# Raspberry_pi_shild_v1.net
KiCad netlist of a schematic drawn in EAGLE
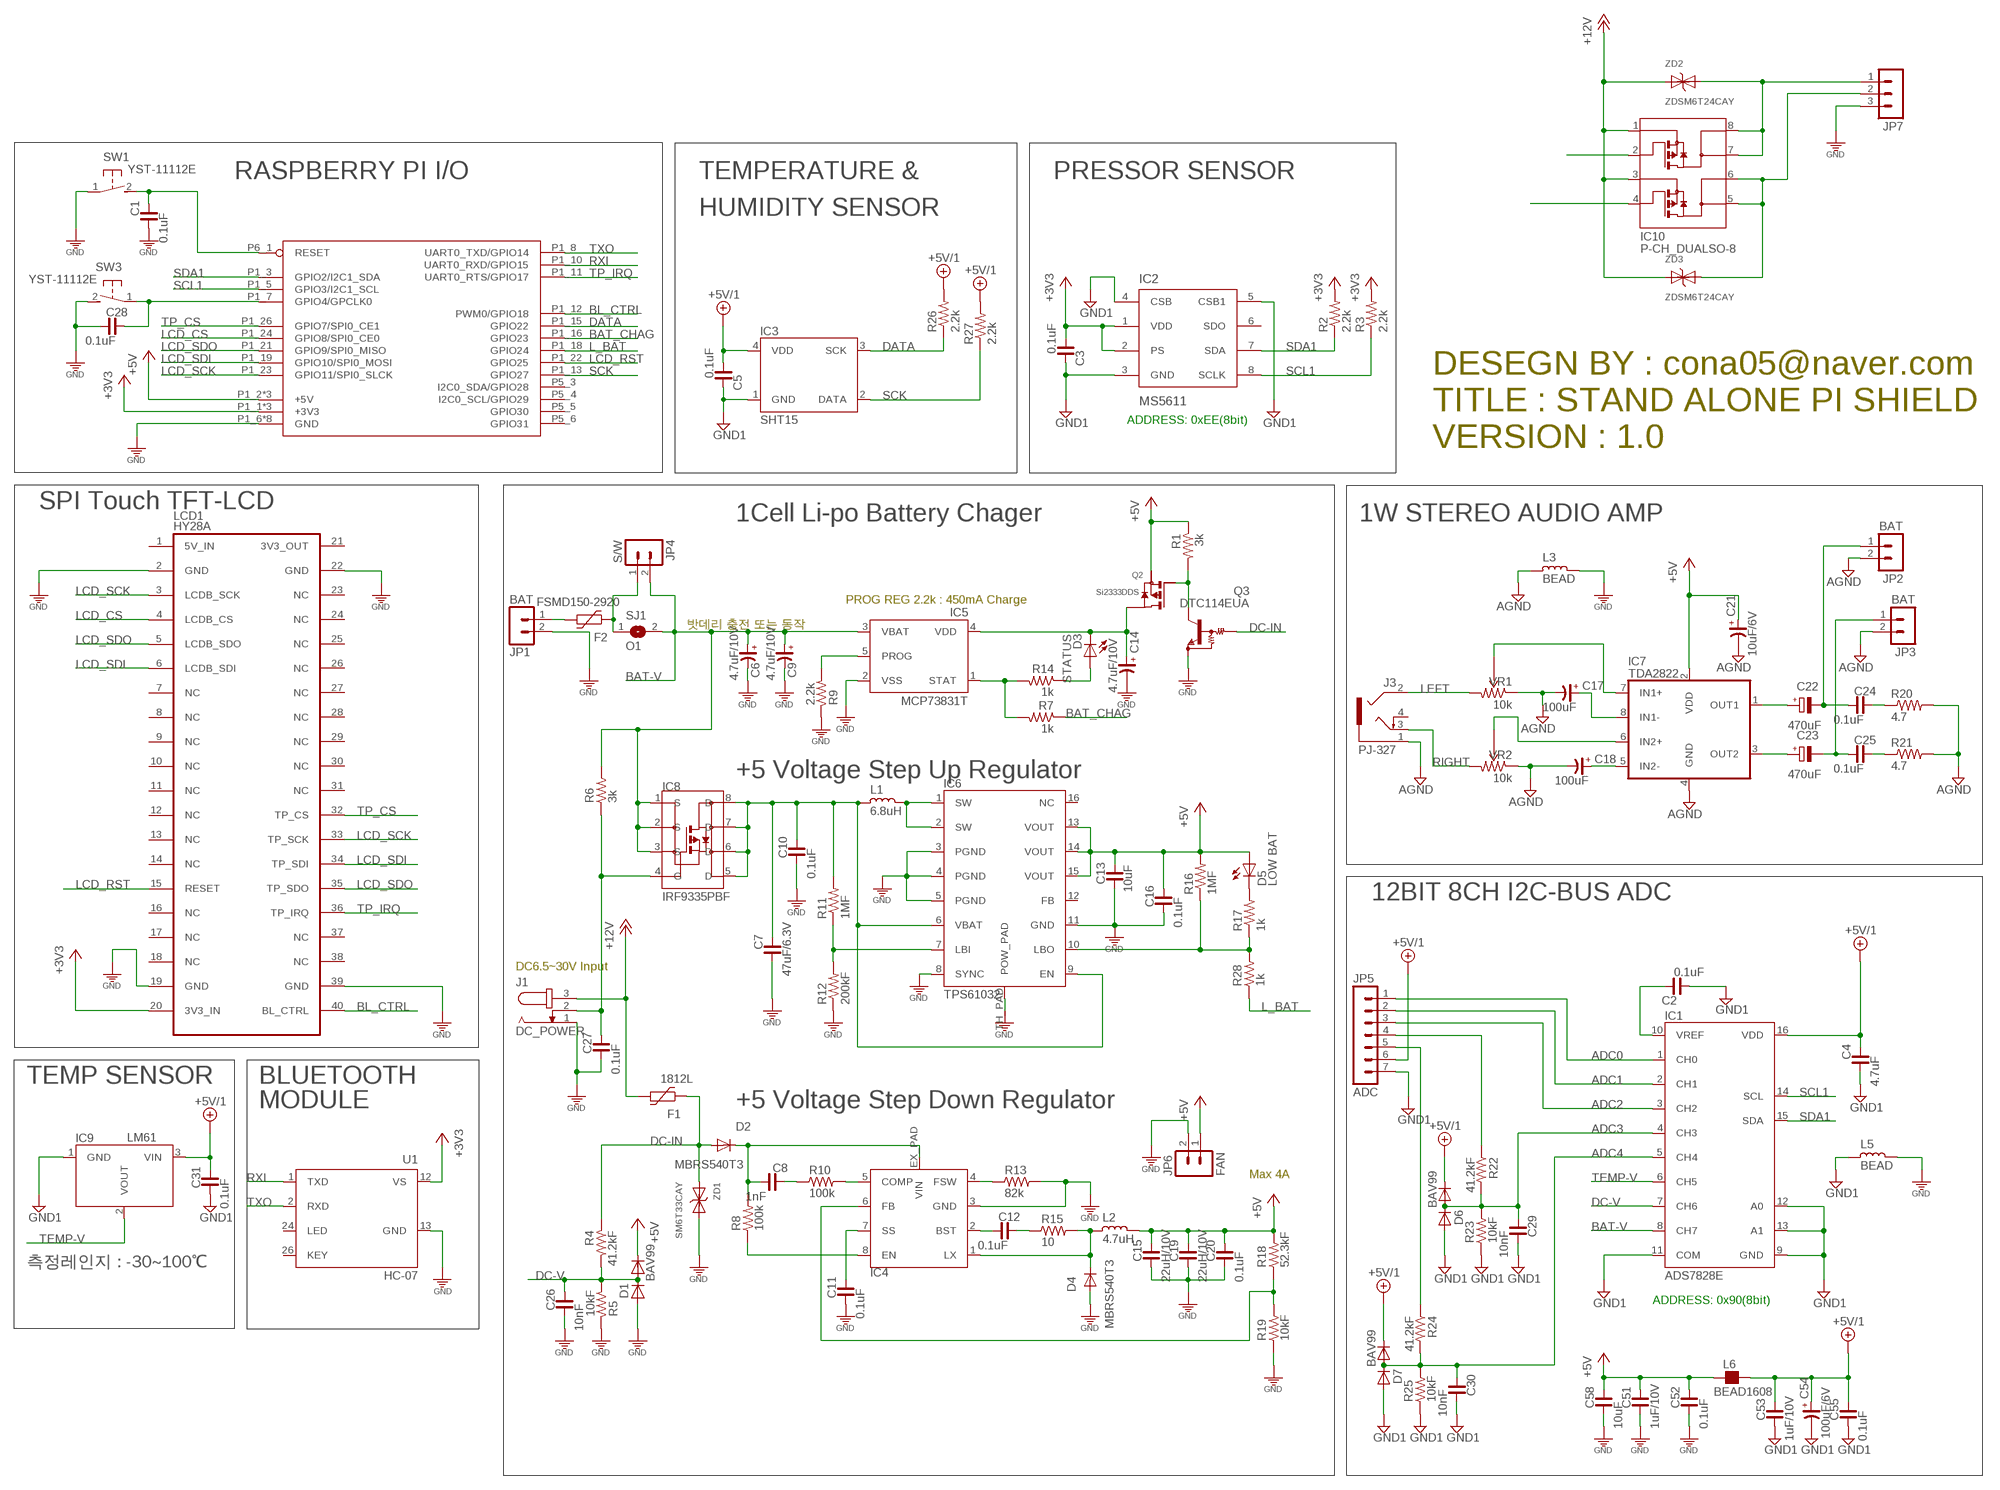
[diagram p0: schematic, sheet 1]

(export (version "E")
  (design (tool "Eeschema 10.0.6"))
  (components
    (comp (ref "C1")
      (value "0.1uF")
      (footprint "eagle-import:C0603")
      (libsource (lib "eagle-import") (part "C_0603"))
    )
    (comp (ref "C2")
      (value "0.1uF")
      (footprint "eagle-import:C0603")
      (libsource (lib "eagle-import") (part "C_0603"))
    )
    (comp (ref "C3")
      (value "0.1uF")
      (footprint "eagle-import:C0603")
      (libsource (lib "eagle-import") (part "C_0603"))
    )
    (comp (ref "C4")
      (value "4.7uF")
      (footprint "eagle-import:C0805")
      (libsource (lib "eagle-import") (part "C_0805"))
    )
    (comp (ref "C5")
      (value "0.1uF")
      (footprint "eagle-import:C0603")
      (libsource (lib "eagle-import") (part "C_0603"))
    )
    (comp (ref "C6")
      (value "4.7uF/10V")
      (footprint "eagle-import:C3216-18_T")
      (libsource (lib "eagle-import") (part "CP_3216-18"))
    )
    (comp (ref "C7")
      (value "47uF/6.3V")
      (footprint "eagle-import:C3216")
      (libsource (lib "eagle-import") (part "C_3216"))
    )
    (comp (ref "C8")
      (value "1nF")
      (footprint "eagle-import:C0603")
      (libsource (lib "eagle-import") (part "C_0603"))
    )
    (comp (ref "C9")
      (value "4.7uF/10V")
      (footprint "eagle-import:C3216-18_T")
      (libsource (lib "eagle-import") (part "CP_3216-18"))
    )
    (comp (ref "C10")
      (value "0.1uF")
      (footprint "eagle-import:C0603")
      (libsource (lib "eagle-import") (part "C_0603"))
    )
    (comp (ref "C11")
      (value "0.1uF")
      (footprint "eagle-import:C0603")
      (libsource (lib "eagle-import") (part "C_0603"))
    )
    (comp (ref "C12")
      (value "0.1uF")
      (footprint "eagle-import:C0603")
      (libsource (lib "eagle-import") (part "C_0603"))
    )
    (comp (ref "C13")
      (value "10uF")
      (footprint "eagle-import:C2012")
      (libsource (lib "eagle-import") (part "C_2012"))
    )
    (comp (ref "C14")
      (value "4.7uF/10V")
      (footprint "eagle-import:C3216-18_T")
      (libsource (lib "eagle-import") (part "CP_3216-18"))
    )
    (comp (ref "C15")
      (value "22uH/10V")
      (footprint "eagle-import:C3216")
      (libsource (lib "eagle-import") (part "C_3216"))
    )
    (comp (ref "C16")
      (value "0.1uF")
      (footprint "eagle-import:C0603")
      (libsource (lib "eagle-import") (part "C_0603"))
    )
    (comp (ref "C17")
      (value "100uF")
      (footprint "eagle-import:C3528-21_T")
      (libsource (lib "eagle-import") (part "CP_3528-21"))
    )
    (comp (ref "C18")
      (value "100uF")
      (footprint "eagle-import:C3528-21_T")
      (libsource (lib "eagle-import") (part "CP_3528-21"))
    )
    (comp (ref "C19")
      (value "22uH/10V")
      (footprint "eagle-import:C3216")
      (libsource (lib "eagle-import") (part "C_3216"))
    )
    (comp (ref "C20")
      (value "0.1uF")
      (footprint "eagle-import:C0603")
      (libsource (lib "eagle-import") (part "C_0603"))
    )
    (comp (ref "C21")
      (value "10uF/6V")
      (footprint "eagle-import:C3216-18_T")
      (libsource (lib "eagle-import") (part "CP_3216-18"))
    )
    (comp (ref "C22")
      (value "470uF")
      (footprint "eagle-import:D_7343-31W")
      (libsource (lib "eagle-import") (part "CPOL-EUD/7343-31W"))
    )
    (comp (ref "C23")
      (value "470uF")
      (footprint "eagle-import:D_7343-31W")
      (libsource (lib "eagle-import") (part "CPOL-EUD/7343-31W"))
    )
    (comp (ref "C24")
      (value "0.1uF")
      (footprint "eagle-import:C0603")
      (libsource (lib "eagle-import") (part "C_0603"))
    )
    (comp (ref "C25")
      (value "0.1uF")
      (footprint "eagle-import:C0603")
      (libsource (lib "eagle-import") (part "C_0603"))
    )
    (comp (ref "C26")
      (value "10nF")
      (footprint "eagle-import:C0603")
      (libsource (lib "eagle-import") (part "C_0603"))
    )
    (comp (ref "C27")
      (value "0.1uF")
      (footprint "eagle-import:C0603")
      (libsource (lib "eagle-import") (part "C_0603"))
    )
    (comp (ref "C28")
      (value "0.1uF")
      (footprint "eagle-import:C0603")
      (libsource (lib "eagle-import") (part "C_0603"))
    )
    (comp (ref "C29")
      (value "10nF")
      (footprint "eagle-import:C0603")
      (libsource (lib "eagle-import") (part "C_0603"))
    )
    (comp (ref "C30")
      (value "10nF")
      (footprint "eagle-import:C0603")
      (libsource (lib "eagle-import") (part "C_0603"))
    )
    (comp (ref "C31")
      (value "0.1uF")
      (footprint "eagle-import:C0603")
      (libsource (lib "eagle-import") (part "C_0603"))
    )
    (comp (ref "C51")
      (value "1uF/10V")
      (footprint "eagle-import:C0603")
      (libsource (lib "eagle-import") (part "C_0603"))
    )
    (comp (ref "C52")
      (value "0.1uF")
      (footprint "eagle-import:C0603")
      (libsource (lib "eagle-import") (part "C_0603"))
    )
    (comp (ref "C53")
      (value "1uF/10V")
      (footprint "eagle-import:C0603")
      (libsource (lib "eagle-import") (part "C_0603"))
    )
    (comp (ref "C54")
      (value "100uF/6V")
      (footprint "eagle-import:C3528-21_T")
      (libsource (lib "eagle-import") (part "CP_3528-21"))
    )
    (comp (ref "C55")
      (value "0.1uF")
      (footprint "eagle-import:C0603")
      (libsource (lib "eagle-import") (part "C_0603"))
    )
    (comp (ref "C58")
      (value "10uF")
      (footprint "eagle-import:C0805")
      (libsource (lib "eagle-import") (part "C_0805"))
    )
    (comp (ref "D1")
      (value "BAV99")
      (footprint "eagle-import:SOT23")
      (libsource (lib "eagle-import") (part "BAV99"))
    )
    (comp (ref "D2")
      (value "MBRS540T3")
      (footprint "eagle-import:SMC")
      (libsource (lib "eagle-import") (part "DIODE-SMC"))
    )
    (comp (ref "D3")
      (value "STATUS")
      (footprint "eagle-import:LED3MM")
      (libsource (lib "eagle-import") (part "LED3MM"))
    )
    (comp (ref "D4")
      (value "MBRS540T3")
      (footprint "eagle-import:SMC")
      (libsource (lib "eagle-import") (part "DIODE-SMC"))
    )
    (comp (ref "D5")
      (value "LOW BAT")
      (footprint "eagle-import:LED3MM")
      (libsource (lib "eagle-import") (part "LED3MM"))
    )
    (comp (ref "D6")
      (value "BAV99")
      (footprint "eagle-import:SOT23")
      (libsource (lib "eagle-import") (part "BAV99"))
    )
    (comp (ref "D7")
      (value "BAV99")
      (footprint "eagle-import:SOT23")
      (libsource (lib "eagle-import") (part "BAV99"))
    )
    (comp (ref "F1")
      (value "1812L")
      (footprint "eagle-import:1812L")
      (libsource (lib "eagle-import") (part "1812L"))
    )
    (comp (ref "F2")
      (value "FSMD150-2920")
      (footprint "eagle-import:1812L")
      (libsource (lib "eagle-import") (part "1812L"))
    )
    (comp (ref "IC1")
      (value "ADS7828E")
      (footprint "eagle-import:R-PDSO-G16")
      (libsource (lib "eagle-import") (part "ADS7828"))
    )
    (comp (ref "IC2")
      (value "MS5611")
      (footprint "eagle-import:LCP8")
      (libsource (lib "eagle-import") (part "MS5611"))
    )
    (comp (ref "IC3")
      (value "SHT15")
      (footprint "eagle-import:SHT1X")
      (libsource (lib "eagle-import") (part "SHT15"))
    )
    (comp (ref "IC4")
      (value "AOZ1284PI")
      (footprint "eagle-import:S08-EP1")
      (libsource (lib "eagle-import") (part "AOZ1284PI"))
    )
    (comp (ref "IC5")
      (value "MCP73831T")
      (footprint "eagle-import:SOT23-5L@1")
      (libsource (lib "eagle-import") (part "MCP73831T"))
    )
    (comp (ref "IC6")
      (value "TPS61032")
      (footprint "eagle-import:R-PDSO-G16-TH_PAD")
      (libsource (lib "eagle-import") (part "TPS61032"))
    )
    (comp (ref "IC7")
      (value "TDA2822")
      (footprint "eagle-import:SO08")
      (libsource (lib "eagle-import") (part "TDA2822"))
    )
    (comp (ref "IC8")
      (value "IRF9335PBF")
      (footprint "eagle-import:SO08")
      (libsource (lib "eagle-import") (part "HEXFET_P"))
    )
    (comp (ref "IC9")
      (value "LM61")
      (footprint "eagle-import:TO92-")
      (libsource (lib "eagle-import") (part "LM61"))
    )
    (comp (ref "IC10")
      (value "P-CH_DUALSO-8")
      (footprint "eagle-import:SO08-1")
      (libsource (lib "eagle-import") (part "P-CH_DUALSO-8"))
    )
    (comp (ref "J1")
      (value "DC_POWER")
      (footprint "eagle-import:SPC4077")
      (libsource (lib "eagle-import") (part "JACK-PLUG0"))
    )
    (comp (ref "J3")
      (value "PJ-327")
      (footprint "eagle-import:PJ-327-2")
      (libsource (lib "eagle-import") (part "AUDIO_JACK2"))
    )
    (comp (ref "JP1")
      (value "BAT")
      (footprint "eagle-import:MA02-MOL-R")
      (libsource (lib "eagle-import") (part "MA02MOL-R"))
    )
    (comp (ref "JP2")
      (value "BAT")
      (footprint "eagle-import:MA02-MOL-R")
      (libsource (lib "eagle-import") (part "MA02MOL-R"))
    )
    (comp (ref "JP3")
      (value "BAT")
      (footprint "eagle-import:MA02-MOL-R")
      (libsource (lib "eagle-import") (part "MA02MOL-R"))
    )
    (comp (ref "JP4")
      (value "S/W")
      (footprint "eagle-import:MA02-MOL-R")
      (libsource (lib "eagle-import") (part "MA02MOL-R"))
    )
    (comp (ref "JP5")
      (value "ADC")
      (footprint "eagle-import:MA07-1T")
      (libsource (lib "eagle-import") (part "MA07-1"))
    )
    (comp (ref "JP6")
      (value "FAN")
      (footprint "eagle-import:MA02-MOL-R")
      (libsource (lib "eagle-import") (part "MA02MOL-R"))
    )
    (comp (ref "JP7")
      (value "MA03-1SMALL")
      (footprint "eagle-import:MA03-1-S")
      (libsource (lib "eagle-import") (part "MA03-1SMALL"))
    )
    (comp (ref "L1")
      (value "6.8uH")
      (footprint "eagle-import:L4545")
      (libsource (lib "eagle-import") (part "L_4545"))
    )
    (comp (ref "L2")
      (value "4.7uH")
      (footprint "eagle-import:L4545")
      (libsource (lib "eagle-import") (part "L_4545"))
    )
    (comp (ref "L3")
      (value "BEAD")
      (footprint "eagle-import:L0603")
      (libsource (lib "eagle-import") (part "L_0603"))
    )
    (comp (ref "L5")
      (value "BEAD")
      (footprint "eagle-import:L0603")
      (libsource (lib "eagle-import") (part "L_0603"))
    )
    (comp (ref "L6")
      (value "BEAD1608")
      (footprint "eagle-import:L0603")
      (libsource (lib "eagle-import") (part "FB_0603"))
    )
    (comp (ref "LCD1")
      (value "HY28A")
      (footprint "eagle-import:HY28A")
      (libsource (lib "eagle-import") (part "HY28A"))
    )
    (comp (ref "Q2")
      (value "Si2333DDS")
      (footprint "eagle-import:SOT23")
      (libsource (lib "eagle-import") (part "P-FET"))
    )
    (comp (ref "Q3")
      (value "DTC114EUA")
      (footprint "eagle-import:SC59-BEC")
      (libsource (lib "eagle-import") (part "DTC114EUA"))
    )
    (comp (ref "R1")
      (value "3k")
      (footprint "eagle-import:R0603")
      (libsource (lib "eagle-import") (part "R_0603"))
    )
    (comp (ref "R2")
      (value "2.2k")
      (footprint "eagle-import:R0603")
      (libsource (lib "eagle-import") (part "R-US_R1608"))
    )
    (comp (ref "R3")
      (value "2.2k")
      (footprint "eagle-import:R0603")
      (libsource (lib "eagle-import") (part "R-US_R1608"))
    )
    (comp (ref "R4")
      (value "41.2kF")
      (footprint "eagle-import:R0603")
      (libsource (lib "eagle-import") (part "R_0603"))
    )
    (comp (ref "R5")
      (value "10kF")
      (footprint "eagle-import:R0603")
      (libsource (lib "eagle-import") (part "R_0603"))
    )
    (comp (ref "R6")
      (value "3k")
      (footprint "eagle-import:R0603")
      (libsource (lib "eagle-import") (part "R_0603"))
    )
    (comp (ref "R7")
      (value "1k")
      (footprint "eagle-import:R0603")
      (libsource (lib "eagle-import") (part "R_0603"))
    )
    (comp (ref "R8")
      (value "100k")
      (footprint "eagle-import:R0603")
      (libsource (lib "eagle-import") (part "R_0603"))
    )
    (comp (ref "R9")
      (value "2.2k")
      (footprint "eagle-import:R0603")
      (libsource (lib "eagle-import") (part "R_0603"))
    )
    (comp (ref "R10")
      (value "100k")
      (footprint "eagle-import:R0603")
      (libsource (lib "eagle-import") (part "R_0603"))
    )
    (comp (ref "R11")
      (value "1MF")
      (footprint "eagle-import:R0603")
      (libsource (lib "eagle-import") (part "R-US_R1608"))
    )
    (comp (ref "R12")
      (value "200kF")
      (footprint "eagle-import:R0603")
      (libsource (lib "eagle-import") (part "R-US_R1608"))
    )
    (comp (ref "R13")
      (value "82k")
      (footprint "eagle-import:R0603")
      (libsource (lib "eagle-import") (part "R_0603"))
    )
    (comp (ref "R14")
      (value "1k")
      (footprint "eagle-import:R0603")
      (libsource (lib "eagle-import") (part "R_0603"))
    )
    (comp (ref "R15")
      (value "10")
      (footprint "eagle-import:R0603")
      (libsource (lib "eagle-import") (part "R_0603"))
    )
    (comp (ref "R16")
      (value "1MF")
      (footprint "eagle-import:R0603")
      (libsource (lib "eagle-import") (part "R-US_R1608"))
    )
    (comp (ref "R17")
      (value "1k")
      (footprint "eagle-import:R0603")
      (libsource (lib "eagle-import") (part "R-US_R1608"))
    )
    (comp (ref "R18")
      (value "52.3kF")
      (footprint "eagle-import:R0603")
      (libsource (lib "eagle-import") (part "R_0603"))
    )
    (comp (ref "R19")
      (value "10kF")
      (footprint "eagle-import:R0603")
      (libsource (lib "eagle-import") (part "R_0603"))
    )
    (comp (ref "R20")
      (value "4.7")
      (footprint "eagle-import:R0603")
      (libsource (lib "eagle-import") (part "R-US_R1608"))
    )
    (comp (ref "R21")
      (value "4.7")
      (footprint "eagle-import:R0603")
      (libsource (lib "eagle-import") (part "R-US_R1608"))
    )
    (comp (ref "R22")
      (value "41.2kF")
      (footprint "eagle-import:R0603")
      (libsource (lib "eagle-import") (part "R_0603"))
    )
    (comp (ref "R23")
      (value "10kF")
      (footprint "eagle-import:R0603")
      (libsource (lib "eagle-import") (part "R_0603"))
    )
    (comp (ref "R24")
      (value "41.2kF")
      (footprint "eagle-import:R0603")
      (libsource (lib "eagle-import") (part "R_0603"))
    )
    (comp (ref "R25")
      (value "10kF")
      (footprint "eagle-import:R0603")
      (libsource (lib "eagle-import") (part "R_0603"))
    )
    (comp (ref "R26")
      (value "2.2k")
      (footprint "eagle-import:R0603")
      (libsource (lib "eagle-import") (part "R-US_R1608"))
    )
    (comp (ref "R27")
      (value "2.2k")
      (footprint "eagle-import:R0603")
      (libsource (lib "eagle-import") (part "R-US_R1608"))
    )
    (comp (ref "R28")
      (value "1k")
      (footprint "eagle-import:R0603")
      (libsource (lib "eagle-import") (part "R_0603"))
    )
    (comp (ref "SJ1") (value "O1") (footprint "eagle-import:SJ") (libsource (lib "eagle-import") (part "SJ")))
    (comp (ref "SW1")
      (value "YST-11112E")
      (footprint "eagle-import:YST-1112E")
      (libsource (lib "eagle-import") (part "YST-11112E"))
    )
    (comp (ref "SW3")
      (value "YST-11112E")
      (footprint "eagle-import:YST-1112E")
      (libsource (lib "eagle-import") (part "YST-11112E"))
    )
    (comp (ref "U$1")
      (value "RPI-B-V2NO_SHIELD")
      (footprint "eagle-import:RPI-B-V2")
      (libsource (lib "eagle-import") (part "RPI-B-V2NO_SHIELD"))
    )
    (comp (ref "U1")
      (value "HC-07")
      (footprint "eagle-import:HC-06")
      (libsource (lib "eagle-import") (part "HC-06_MODULEFULL"))
    )
    (comp (ref "VR1")
      (value "10k")
      (footprint "eagle-import:R-TRIMMER-3313J")
      (libsource (lib "eagle-import") (part "R-TRIMMER-SMD3313"))
    )
    (comp (ref "VR2")
      (value "10k")
      (footprint "eagle-import:R-TRIMMER-3313J")
      (libsource (lib "eagle-import") (part "R-TRIMMER-SMD3313"))
    )
    (comp (ref "ZD1")
      (value "SM6T33CAY")
      (footprint "eagle-import:SMB")
      (libsource (lib "eagle-import") (part "ZDSM6T33CAY"))
    )
    (comp (ref "ZD2")
      (value "ZDSM6T24CAY")
      (footprint "eagle-import:SMB")
      (libsource (lib "eagle-import") (part "ZDSM6T33CAY"))
    )
    (comp (ref "ZD3")
      (value "ZDSM6T24CAY")
      (footprint "eagle-import:SMB")
      (libsource (lib "eagle-import") (part "ZDSM6T33CAY"))
    )
  )
  (nets
    (net (code "1") (name "+3V3") (class "Default")
      (node (ref "C3") (pin "2") (pinfunction "2_2") (pintype "passive"))
      (node (ref "IC2") (pin "1") (pinfunction "VDD_1") (pintype "power_in"))
      (node (ref "IC2") (pin "2") (pinfunction "PS_2") (pintype "power_in"))
      (node (ref "LCD1") (pin "20") (pinfunction "3V3_IN_20") (pintype "passive"))
      (node (ref "R2") (pin "2") (pinfunction "2_2") (pintype "passive"))
      (node (ref "R3") (pin "2") (pinfunction "2_2") (pintype "passive"))
      (node (ref "U$1") (pin "P1_1") (pinfunction "+3V3_P1_1") (pintype "power_in"))
      (node (ref "U$1") (pin "P1_17") (pinfunction "+3V3_P1_17") (pintype "power_in"))
      (node (ref "U$1") (pin "P5_2") (pinfunction "+3V3_P5_2") (pintype "power_in"))
      (node (ref "U1") (pin "12") (pinfunction "VS_12") (pintype "power_in"))
    )
    (net (code "2") (name "+5V") (class "Default")
      (node (ref "C13") (pin "1") (pinfunction "1_1") (pintype "passive"))
      (node (ref "C15") (pin "1") (pinfunction "1_1") (pintype "passive"))
      (node (ref "C16") (pin "1") (pinfunction "1_1") (pintype "passive"))
      (node (ref "C19") (pin "1") (pinfunction "1_1") (pintype "passive"))
      (node (ref "C20") (pin "1") (pinfunction "1_1") (pintype "passive"))
      (node (ref "C21") (pin "+") (pinfunction "+_+") (pintype "passive"))
      (node (ref "C51") (pin "1") (pinfunction "1_1") (pintype "passive"))
      (node (ref "C52") (pin "1") (pinfunction "1_1") (pintype "passive"))
      (node (ref "C58") (pin "1") (pinfunction "1_1") (pintype "passive"))
      (node (ref "D1") (pin "S") (pinfunction "C_S") (pintype "passive"))
      (node (ref "D5") (pin "A") (pinfunction "A_A") (pintype "passive"))
      (node (ref "IC6") (pin "13") (pinfunction "VOUT_13") (pintype "passive"))
      (node (ref "IC6") (pin "14") (pinfunction "VOUT_14") (pintype "passive"))
      (node (ref "IC6") (pin "15") (pinfunction "VOUT_15") (pintype "passive"))
      (node (ref "IC7") (pin "2") (pinfunction "VDD_2") (pintype "power_in"))
      (node (ref "JP6") (pin "1") (pinfunction "1_1") (pintype "passive"))
      (node (ref "L2") (pin "1") (pinfunction "1_1") (pintype "passive"))
      (node (ref "L6") (pin "1") (pinfunction "1_1") (pintype "passive"))
      (node (ref "Q2") (pin "S") (pinfunction "SOURCE_S") (pintype "bidirectional"))
      (node (ref "R1") (pin "1") (pinfunction "1_1") (pintype "passive"))
      (node (ref "R16") (pin "2") (pinfunction "2_2") (pintype "passive"))
      (node (ref "R18") (pin "2") (pinfunction "2_2") (pintype "passive"))
      (node (ref "U$1") (pin "P1_2") (pinfunction "+5V_P1_2") (pintype "power_in"))
      (node (ref "U$1") (pin "P1_4") (pinfunction "+5V_P1_4") (pintype "power_in"))
      (node (ref "U$1") (pin "P5_1") (pinfunction "+5V_P5_1") (pintype "power_in"))
    )
    (net (code "3") (name "+5V{slash}1") (class "Default")
      (node (ref "C31") (pin "1") (pinfunction "1_1") (pintype "passive"))
      (node (ref "C4") (pin "1") (pinfunction "1_1") (pintype "passive"))
      (node (ref "C5") (pin "2") (pinfunction "2_2") (pintype "passive"))
      (node (ref "C53") (pin "1") (pinfunction "1_1") (pintype "passive"))
      (node (ref "C54") (pin "+") (pinfunction "+_+") (pintype "passive"))
      (node (ref "C55") (pin "1") (pinfunction "1_1") (pintype "passive"))
      (node (ref "D6") (pin "S") (pinfunction "C_S") (pintype "passive"))
      (node (ref "D7") (pin "S") (pinfunction "C_S") (pintype "passive"))
      (node (ref "IC1") (pin "16") (pinfunction "VDD_16") (pintype "power_in"))
      (node (ref "IC3") (pin "4") (pinfunction "VDD_4") (pintype "power_in"))
      (node (ref "IC9") (pin "3") (pinfunction "VIN_3") (pintype "power_in"))
      (node (ref "JP5") (pin "6") (pinfunction "6_6") (pintype "passive"))
      (node (ref "L6") (pin "2") (pinfunction "2_2") (pintype "passive"))
      (node (ref "R26") (pin "2") (pinfunction "2_2") (pintype "passive"))
      (node (ref "R27") (pin "2") (pinfunction "2_2") (pintype "passive"))
    )
    (net (code "4") (name "+12V") (class "Default")
      (node (ref "F1") (pin "P$2") (pinfunction "2_P$2") (pintype "passive"))
      (node (ref "IC10") (pin "1") (pinfunction "1_1") (pintype "power_in"))
      (node (ref "IC10") (pin "3") (pinfunction "3_3") (pintype "power_in"))
      (node (ref "J1") (pin "3") (pinfunction "3_3") (pintype "passive"))
      (node (ref "ZD2") (pin "A") (pinfunction "A_A") (pintype "passive"))
      (node (ref "ZD3") (pin "A") (pinfunction "A_A") (pintype "passive"))
    )
    (net (code "5") (name "/ADC0") (class "Default")
      (node (ref "IC1") (pin "1") (pinfunction "CH0_1") (pintype "input"))
      (node (ref "JP5") (pin "1") (pinfunction "1_1") (pintype "passive"))
    )
    (net (code "6") (name "/ADC1") (class "Default")
      (node (ref "IC1") (pin "2") (pinfunction "CH1_2") (pintype "input"))
      (node (ref "JP5") (pin "2") (pinfunction "2_2") (pintype "passive"))
    )
    (net (code "7") (name "/ADC2") (class "Default")
      (node (ref "IC1") (pin "3") (pinfunction "CH2_3") (pintype "input"))
      (node (ref "JP5") (pin "3") (pinfunction "3_3") (pintype "passive"))
    )
    (net (code "8") (name "/ADC3") (class "Default")
      (node (ref "C29") (pin "1") (pinfunction "1_1") (pintype "passive"))
      (node (ref "D6") (pin "D") (pinfunction "AC_D") (pintype "passive"))
      (node (ref "IC1") (pin "4") (pinfunction "CH3_4") (pintype "input"))
      (node (ref "R22") (pin "2") (pinfunction "2_2") (pintype "passive"))
      (node (ref "R23") (pin "2") (pinfunction "2_2") (pintype "passive"))
    )
    (net (code "9") (name "/ADC4") (class "Default")
      (node (ref "C30") (pin "1") (pinfunction "1_1") (pintype "passive"))
      (node (ref "D7") (pin "D") (pinfunction "AC_D") (pintype "passive"))
      (node (ref "IC1") (pin "5") (pinfunction "CH4_5") (pintype "input"))
      (node (ref "R24") (pin "2") (pinfunction "2_2") (pintype "passive"))
      (node (ref "R25") (pin "2") (pinfunction "2_2") (pintype "passive"))
    )
    (net (code "10") (name "/BAT-V") (class "Default")
      (node (ref "C6") (pin "+") (pinfunction "+_+") (pintype "passive"))
      (node (ref "C9") (pin "+") (pinfunction "+_+") (pintype "passive"))
      (node (ref "IC1") (pin "8") (pinfunction "CH7_8") (pintype "input"))
      (node (ref "IC5") (pin "3") (pinfunction "VBAT_3") (pintype "power_in"))
      (node (ref "IC8") (pin "1") (pinfunction "S_1") (pintype "passive"))
      (node (ref "IC8") (pin "2") (pinfunction "S_2") (pintype "passive"))
      (node (ref "IC8") (pin "3") (pinfunction "S_3") (pintype "passive"))
      (node (ref "JP4") (pin "2") (pinfunction "2_2") (pintype "passive"))
      (node (ref "R6") (pin "2") (pinfunction "2_2") (pintype "passive"))
      (node (ref "SJ1") (pin "2") (pinfunction "2_2") (pintype "passive"))
    )
    (net (code "11") (name "/BAT_CHAG") (class "Default")
      (node (ref "R7") (pin "1") (pinfunction "1_1") (pintype "passive"))
      (node (ref "U$1") (pin "P1_16") (pinfunction "GPIO23_P1_16") (pintype "bidirectional"))
    )
    (net (code "12") (name "/BL_CTRL") (class "Default")
      (node (ref "LCD1") (pin "40") (pinfunction "BL_CTRL_40") (pintype "passive"))
      (node (ref "U$1") (pin "P1_12") (pinfunction "PWM0/GPIO18_P1_12") (pintype "bidirectional"))
    )
    (net (code "13") (name "/DATA") (class "Default")
      (node (ref "IC3") (pin "3") (pinfunction "SCK_3") (pintype "input"))
      (node (ref "R26") (pin "1") (pinfunction "1_1") (pintype "passive"))
      (node (ref "U$1") (pin "P1_15") (pinfunction "GPIO22_P1_15") (pintype "bidirectional"))
    )
    (net (code "14") (name "/DC-IN") (class "Default")
      (node (ref "D2") (pin "A") (pinfunction "A_A") (pintype "passive"))
      (node (ref "F1") (pin "P$1") (pinfunction "1_P$1") (pintype "passive"))
      (node (ref "Q3") (pin "2") (pinfunction "IN_2") (pintype "passive"))
      (node (ref "R4") (pin "1") (pinfunction "1_1") (pintype "passive"))
      (node (ref "ZD1") (pin "A") (pinfunction "A_A") (pintype "passive"))
    )
    (net (code "15") (name "/DC-V") (class "Default")
      (node (ref "C26") (pin "1") (pinfunction "1_1") (pintype "passive"))
      (node (ref "D1") (pin "D") (pinfunction "AC_D") (pintype "passive"))
      (node (ref "IC1") (pin "7") (pinfunction "CH6_7") (pintype "input"))
      (node (ref "R4") (pin "2") (pinfunction "2_2") (pintype "passive"))
      (node (ref "R5") (pin "2") (pinfunction "2_2") (pintype "passive"))
    )
    (net (code "16") (name "/GPIO30") (class "Default")
      (node (ref "U$1") (pin "P5_5") (pinfunction "GPIO30_P5_5") (pintype "power_in"))
    )
    (net (code "17") (name "/GPIO31") (class "Default")
      (node (ref "U$1") (pin "P5_6") (pinfunction "GPIO31_P5_6") (pintype "power_in"))
    )
    (net (code "18") (name "/I2C0_SCL{slash}GPIO29") (class "Default")
      (node (ref "U$1") (pin "P5_4") (pinfunction "I2C0_SCL/GPIO29_P5_4") (pintype "power_in"))
    )
    (net (code "19") (name "/I2C0_SDA{slash}GPIO28") (class "Default")
      (node (ref "U$1") (pin "P5_3") (pinfunction "I2C0_SDA/GPIO28_P5_3") (pintype "power_in"))
    )
    (net (code "20") (name "/LCD_CS") (class "Default")
      (node (ref "LCD1") (pin "4") (pinfunction "LCDB_CS_4") (pintype "passive"))
      (node (ref "U$1") (pin "P1_24") (pinfunction "GPIO8/SPI0_CE0_P1_24") (pintype "bidirectional"))
    )
    (net (code "21") (name "/LCD_RST") (class "Default")
      (node (ref "LCD1") (pin "15") (pinfunction "RESET_15") (pintype "passive"))
      (node (ref "U$1") (pin "P1_22") (pinfunction "GPIO25_P1_22") (pintype "bidirectional"))
    )
    (net (code "22") (name "/LCD_SCK") (class "Default")
      (node (ref "LCD1") (pin "3") (pinfunction "LCDB_SCK_3") (pintype "passive"))
      (node (ref "LCD1") (pin "33") (pinfunction "TP_SCK_33") (pintype "passive"))
      (node (ref "U$1") (pin "P1_23") (pinfunction "GPIO11/SPI0_SLCK_P1_23") (pintype "bidirectional"))
    )
    (net (code "23") (name "/LCD_SDI") (class "Default")
      (node (ref "LCD1") (pin "34") (pinfunction "TP_SDI_34") (pintype "passive"))
      (node (ref "LCD1") (pin "6") (pinfunction "LCDB_SDI_6") (pintype "passive"))
      (node (ref "U$1") (pin "P1_19") (pinfunction "GPIO10/SPI0_MOSI_P1_19") (pintype "bidirectional"))
    )
    (net (code "24") (name "/LCD_SDO") (class "Default")
      (node (ref "LCD1") (pin "35") (pinfunction "TP_SDO_35") (pintype "passive"))
      (node (ref "LCD1") (pin "5") (pinfunction "LCDB_SDO_5") (pintype "passive"))
      (node (ref "U$1") (pin "P1_21") (pinfunction "GPIO9/SPI0_MISO_P1_21") (pintype "bidirectional"))
    )
    (net (code "25") (name "/LEFT") (class "Default")
      (node (ref "J3") (pin "2") (pinfunction "2_2") (pintype "passive"))
      (node (ref "VR1") (pin "3") (pinfunction "3_3") (pintype "passive"))
    )
    (net (code "26") (name "/L_BAT") (class "Default")
      (node (ref "R28") (pin "1") (pinfunction "1_1") (pintype "passive"))
      (node (ref "U$1") (pin "P1_18") (pinfunction "GPIO24_P1_18") (pintype "bidirectional"))
    )
    (net (code "27") (name "/RIGHT") (class "Default")
      (node (ref "J3") (pin "3") (pinfunction "3_3") (pintype "passive"))
      (node (ref "VR2") (pin "3") (pinfunction "3_3") (pintype "passive"))
    )
    (net (code "28") (name "/RXI") (class "Default")
      (node (ref "U$1") (pin "P1_10") (pinfunction "UART0_RXD/GPIO15_P1_10") (pintype "bidirectional"))
      (node (ref "U1") (pin "1") (pinfunction "TXD_1") (pintype "output"))
    )
    (net (code "29") (name "/SCK") (class "Default")
      (node (ref "IC3") (pin "2") (pinfunction "DATA_2") (pintype "bidirectional"))
      (node (ref "R27") (pin "1") (pinfunction "1_1") (pintype "passive"))
      (node (ref "U$1") (pin "P1_13") (pinfunction "GPIO27_P1_13") (pintype "bidirectional"))
    )
    (net (code "30") (name "/SCL1") (class "Default")
      (node (ref "IC1") (pin "14") (pinfunction "SCL_14") (pintype "bidirectional"))
      (node (ref "IC2") (pin "8") (pinfunction "SCLK_8") (pintype "input"))
      (node (ref "R3") (pin "1") (pinfunction "1_1") (pintype "passive"))
      (node (ref "U$1") (pin "P1_5") (pinfunction "GPIO3/I2C1_SCL_P1_5") (pintype "bidirectional"))
    )
    (net (code "31") (name "/SDA1") (class "Default")
      (node (ref "IC1") (pin "15") (pinfunction "SDA_15") (pintype "output"))
      (node (ref "IC2") (pin "7") (pinfunction "SDA_7") (pintype "bidirectional"))
      (node (ref "R2") (pin "1") (pinfunction "1_1") (pintype "passive"))
      (node (ref "U$1") (pin "P1_3") (pinfunction "GPIO2/I2C1_SDA_P1_3") (pintype "bidirectional"))
    )
    (net (code "32") (name "/TEMP-V") (class "Default")
      (node (ref "IC1") (pin "6") (pinfunction "CH5_6") (pintype "input"))
      (node (ref "IC9") (pin "2") (pinfunction "VOUT_2") (pintype "output"))
    )
    (net (code "33") (name "/TP_CS") (class "Default")
      (node (ref "LCD1") (pin "32") (pinfunction "TP_CS_32") (pintype "passive"))
      (node (ref "U$1") (pin "P1_26") (pinfunction "GPIO7/SPI0_CE1_P1_26") (pintype "bidirectional"))
    )
    (net (code "34") (name "/TP_IRQ") (class "Default")
      (node (ref "LCD1") (pin "36") (pinfunction "TP_IRQ_36") (pintype "passive"))
      (node (ref "U$1") (pin "P1_11") (pinfunction "UART0_RTS/GPIO17_P1_11") (pintype "bidirectional"))
    )
    (net (code "35") (name "/TXO") (class "Default")
      (node (ref "U$1") (pin "P1_8") (pinfunction "UART0_TXD/GPIO14_P1_8") (pintype "bidirectional"))
      (node (ref "U1") (pin "2") (pinfunction "RXD_2") (pintype "input"))
    )
    (net (code "36") (name "AGND") (class "Default")
      (node (ref "C17") (pin "-") (pinfunction "-_-") (pintype "passive"))
      (node (ref "C18") (pin "-") (pinfunction "-_-") (pintype "passive"))
      (node (ref "C21") (pin "-") (pinfunction "-_-") (pintype "passive"))
      (node (ref "IC7") (pin "4") (pinfunction "GND_4") (pintype "power_in"))
      (node (ref "J3") (pin "1") (pinfunction "1_1") (pintype "passive"))
      (node (ref "JP2") (pin "2") (pinfunction "2_2") (pintype "passive"))
      (node (ref "JP3") (pin "2") (pinfunction "2_2") (pintype "passive"))
      (node (ref "L3") (pin "2") (pinfunction "2_2") (pintype "passive"))
      (node (ref "R20") (pin "2") (pinfunction "2_2") (pintype "passive"))
      (node (ref "R21") (pin "2") (pinfunction "2_2") (pintype "passive"))
      (node (ref "VR1") (pin "1") (pinfunction "1_1") (pintype "passive"))
      (node (ref "VR2") (pin "1") (pinfunction "1_1") (pintype "passive"))
    )
    (net (code "37") (name "GND") (class "Default")
      (node (ref "C1") (pin "2") (pinfunction "2_2") (pintype "passive"))
      (node (ref "C10") (pin "2") (pinfunction "2_2") (pintype "passive"))
      (node (ref "C11") (pin "2") (pinfunction "2_2") (pintype "passive"))
      (node (ref "C13") (pin "2") (pinfunction "2_2") (pintype "passive"))
      (node (ref "C14") (pin "-") (pinfunction "-_-") (pintype "passive"))
      (node (ref "C15") (pin "2") (pinfunction "2_2") (pintype "passive"))
      (node (ref "C16") (pin "2") (pinfunction "2_2") (pintype "passive"))
      (node (ref "C19") (pin "2") (pinfunction "2_2") (pintype "passive"))
      (node (ref "C20") (pin "2") (pinfunction "2_2") (pintype "passive"))
      (node (ref "C26") (pin "2") (pinfunction "2_2") (pintype "passive"))
      (node (ref "C27") (pin "2") (pinfunction "2_2") (pintype "passive"))
      (node (ref "C28") (pin "2") (pinfunction "2_2") (pintype "passive"))
      (node (ref "C51") (pin "2") (pinfunction "2_2") (pintype "passive"))
      (node (ref "C52") (pin "2") (pinfunction "2_2") (pintype "passive"))
      (node (ref "C58") (pin "2") (pinfunction "2_2") (pintype "passive"))
      (node (ref "C6") (pin "-") (pinfunction "-_-") (pintype "passive"))
      (node (ref "C7") (pin "2") (pinfunction "2_2") (pintype "passive"))
      (node (ref "C9") (pin "-") (pinfunction "-_-") (pintype "passive"))
      (node (ref "D1") (pin "G") (pinfunction "A_G") (pintype "passive"))
      (node (ref "D4") (pin "A") (pinfunction "A_A") (pintype "passive"))
      (node (ref "IC4") (pin "3") (pinfunction "GND_3") (pintype "power_in"))
      (node (ref "IC5") (pin "2") (pinfunction "VSS_2") (pintype "power_in"))
      (node (ref "IC6") (pin "11") (pinfunction "GND_11") (pintype "power_in"))
      (node (ref "IC6") (pin "3") (pinfunction "PGND_3") (pintype "power_in"))
      (node (ref "IC6") (pin "4") (pinfunction "PGND_4") (pintype "power_in"))
      (node (ref "IC6") (pin "5") (pinfunction "PGND_5") (pintype "power_in"))
      (node (ref "IC6") (pin "8") (pinfunction "SYNC_8") (pintype "passive"))
      (node (ref "IC6") (pin "TH_PAD") (pinfunction "POW_PAD_TH_PAD") (pintype "power_in"))
      (node (ref "J1") (pin "1") (pinfunction "1_1") (pintype "passive"))
      (node (ref "JP1") (pin "2") (pinfunction "2_2") (pintype "passive"))
      (node (ref "JP6") (pin "2") (pinfunction "2_2") (pintype "passive"))
      (node (ref "JP7") (pin "3") (pinfunction "3_3") (pintype "passive"))
      (node (ref "L3") (pin "1") (pinfunction "1_1") (pintype "passive"))
      (node (ref "L5") (pin "1") (pinfunction "1_1") (pintype "passive"))
      (node (ref "LCD1") (pin "19") (pinfunction "GND_19") (pintype "power_in"))
      (node (ref "LCD1") (pin "2") (pinfunction "GND_2") (pintype "power_in"))
      (node (ref "LCD1") (pin "22") (pinfunction "GND_22") (pintype "power_in"))
      (node (ref "LCD1") (pin "39") (pinfunction "GND_39") (pintype "power_in"))
      (node (ref "Q3") (pin "1") (pinfunction "GND_1") (pintype "passive"))
      (node (ref "R12") (pin "1") (pinfunction "1_1") (pintype "passive"))
      (node (ref "R13") (pin "2") (pinfunction "2_2") (pintype "passive"))
      (node (ref "R19") (pin "1") (pinfunction "1_1") (pintype "passive"))
      (node (ref "R5") (pin "1") (pinfunction "1_1") (pintype "passive"))
      (node (ref "R9") (pin "1") (pinfunction "1_1") (pintype "passive"))
      (node (ref "SW1") (pin "1") (pinfunction "1_1") (pintype "passive"))
      (node (ref "SW3") (pin "2") (pinfunction "2_2") (pintype "passive"))
      (node (ref "U$1") (pin "P1_14") (pinfunction "GND_P1_14") (pintype "power_in"))
      (node (ref "U$1") (pin "P1_20") (pinfunction "GND_P1_20") (pintype "power_in"))
      (node (ref "U$1") (pin "P1_25") (pinfunction "GND_P1_25") (pintype "power_in"))
      (node (ref "U$1") (pin "P1_6") (pinfunction "GND_P1_6") (pintype "power_in"))
      (node (ref "U$1") (pin "P1_9") (pinfunction "GND_P1_9") (pintype "power_in"))
      (node (ref "U$1") (pin "P5_7") (pinfunction "GND_P5_7") (pintype "power_in"))
      (node (ref "U$1") (pin "P5_8") (pinfunction "GND_P5_8") (pintype "power_in"))
      (node (ref "U$1") (pin "P6_2") (pinfunction "GND_P6_2") (pintype "power_in"))
      (node (ref "U1") (pin "13") (pinfunction "GND_13") (pintype "power_in"))
      (node (ref "ZD1") (pin "C") (pinfunction "K_C") (pintype "passive"))
    )
    (net (code "38") (name "GND1") (class "Default")
      (node (ref "C2") (pin "2") (pinfunction "2_2") (pintype "passive"))
      (node (ref "C29") (pin "2") (pinfunction "2_2") (pintype "passive"))
      (node (ref "C3") (pin "1") (pinfunction "1_1") (pintype "passive"))
      (node (ref "C30") (pin "2") (pinfunction "2_2") (pintype "passive"))
      (node (ref "C31") (pin "2") (pinfunction "2_2") (pintype "passive"))
      (node (ref "C4") (pin "2") (pinfunction "2_2") (pintype "passive"))
      (node (ref "C5") (pin "1") (pinfunction "1_1") (pintype "passive"))
      (node (ref "C53") (pin "2") (pinfunction "2_2") (pintype "passive"))
      (node (ref "C54") (pin "-") (pinfunction "-_-") (pintype "passive"))
      (node (ref "C55") (pin "2") (pinfunction "2_2") (pintype "passive"))
      (node (ref "D6") (pin "G") (pinfunction "A_G") (pintype "passive"))
      (node (ref "D7") (pin "G") (pinfunction "A_G") (pintype "passive"))
      (node (ref "IC1") (pin "11") (pinfunction "COM_11") (pintype "power_in"))
      (node (ref "IC1") (pin "12") (pinfunction "A0_12") (pintype "bidirectional"))
      (node (ref "IC1") (pin "13") (pinfunction "A1_13") (pintype "bidirectional"))
      (node (ref "IC1") (pin "9") (pinfunction "GND_9") (pintype "power_in"))
      (node (ref "IC2") (pin "3") (pinfunction "GND_3") (pintype "power_in"))
      (node (ref "IC2") (pin "4") (pinfunction "CSB_4") (pintype "input"))
      (node (ref "IC2") (pin "5") (pinfunction "CSB1_5") (pintype "input"))
      (node (ref "IC3") (pin "1") (pinfunction "GND_1") (pintype "power_in"))
      (node (ref "IC9") (pin "1") (pinfunction "GND_1") (pintype "power_in"))
      (node (ref "JP5") (pin "7") (pinfunction "7_7") (pintype "passive"))
      (node (ref "L5") (pin "2") (pinfunction "2_2") (pintype "passive"))
      (node (ref "R23") (pin "1") (pinfunction "1_1") (pintype "passive"))
      (node (ref "R25") (pin "1") (pinfunction "1_1") (pintype "passive"))
    )
    (net (code "39") (name "Net-(C8-Pad1)") (class "Default")
      (node (ref "C8") (pin "1") (pinfunction "1_1") (pintype "passive"))
      (node (ref "R10") (pin "1") (pinfunction "1_1") (pintype "passive"))
    )
    (net (code "40") (name "Net-(C12-Pad1)") (class "Default")
      (node (ref "C12") (pin "1") (pinfunction "1_1") (pintype "passive"))
      (node (ref "R15") (pin "1") (pinfunction "1_1") (pintype "passive"))
    )
    (net (code "41") (name "Net-(C22-Pad-)") (class "Default")
      (node (ref "C22") (pin "-") (pinfunction "-_-") (pintype "passive"))
      (node (ref "C24") (pin "2") (pinfunction "2_2") (pintype "passive"))
      (node (ref "JP2") (pin "1") (pinfunction "1_1") (pintype "passive"))
    )
    (net (code "42") (name "Net-(C23-Pad-)") (class "Default")
      (node (ref "C23") (pin "-") (pinfunction "-_-") (pintype "passive"))
      (node (ref "C25") (pin "2") (pinfunction "2_2") (pintype "passive"))
      (node (ref "JP3") (pin "1") (pinfunction "1_1") (pintype "passive"))
    )
    (net (code "43") (name "Net-(C24-Pad1)") (class "Default")
      (node (ref "C24") (pin "1") (pinfunction "1_1") (pintype "passive"))
      (node (ref "R20") (pin "1") (pinfunction "1_1") (pintype "passive"))
    )
    (net (code "44") (name "Net-(C25-Pad1)") (class "Default")
      (node (ref "C25") (pin "1") (pinfunction "1_1") (pintype "passive"))
      (node (ref "R21") (pin "1") (pinfunction "1_1") (pintype "passive"))
    )
    (net (code "45") (name "Net-(D3-C)") (class "Default")
      (node (ref "C14") (pin "+") (pinfunction "+_+") (pintype "passive"))
      (node (ref "D3") (pin "K") (pinfunction "C_K") (pintype "passive"))
      (node (ref "IC5") (pin "4") (pinfunction "VDD_4") (pintype "power_in"))
      (node (ref "Q2") (pin "D") (pinfunction "DRAIN_D") (pintype "bidirectional"))
    )
    (net (code "46") (name "Net-(D3-PadA)") (class "Default")
      (node (ref "D3") (pin "A") (pinfunction "A_A") (pintype "passive"))
      (node (ref "R14") (pin "1") (pinfunction "1_1") (pintype "passive"))
    )
    (net (code "47") (name "Net-(D5-C)") (class "Default")
      (node (ref "D5") (pin "K") (pinfunction "C_K") (pintype "passive"))
      (node (ref "R17") (pin "2") (pinfunction "2_2") (pintype "passive"))
    )
    (net (code "48") (name "Net-(F2-1)") (class "Default")
      (node (ref "F2") (pin "P$1") (pinfunction "1_P$1") (pintype "passive"))
      (node (ref "JP4") (pin "1") (pinfunction "1_1") (pintype "passive"))
      (node (ref "SJ1") (pin "1") (pinfunction "1_1") (pintype "passive"))
    )
    (net (code "49") (name "Net-(F2-2)") (class "Default")
      (node (ref "F2") (pin "P$2") (pinfunction "2_P$2") (pintype "passive"))
      (node (ref "JP1") (pin "1") (pinfunction "1_1") (pintype "passive"))
    )
    (net (code "50") (name "Net-(IC1-VREF)") (class "Default")
      (node (ref "C2") (pin "1") (pinfunction "1_1") (pintype "passive"))
      (node (ref "IC1") (pin "10") (pinfunction "VREF_10") (pintype "passive"))
    )
    (net (code "51") (name "Net-(IC4-BST)") (class "Default")
      (node (ref "C12") (pin "2") (pinfunction "2_2") (pintype "passive"))
      (node (ref "IC4") (pin "2") (pinfunction "BST_2") (pintype "passive"))
    )
    (net (code "52") (name "Net-(IC4-COMP)") (class "Default")
      (node (ref "IC4") (pin "5") (pinfunction "COMP_5") (pintype "passive"))
      (node (ref "R10") (pin "2") (pinfunction "2_2") (pintype "passive"))
    )
    (net (code "53") (name "Net-(IC4-EN)") (class "Default")
      (node (ref "IC4") (pin "8") (pinfunction "EN_8") (pintype "passive"))
      (node (ref "R8") (pin "1") (pinfunction "1_1") (pintype "passive"))
    )
    (net (code "54") (name "Net-(IC4-FB)") (class "Default")
      (node (ref "IC4") (pin "6") (pinfunction "FB_6") (pintype "passive"))
      (node (ref "R18") (pin "1") (pinfunction "1_1") (pintype "passive"))
      (node (ref "R19") (pin "2") (pinfunction "2_2") (pintype "passive"))
    )
    (net (code "55") (name "Net-(IC4-FSW)") (class "Default")
      (node (ref "IC4") (pin "4") (pinfunction "FSW_4") (pintype "passive"))
      (node (ref "R13") (pin "1") (pinfunction "1_1") (pintype "passive"))
    )
    (net (code "56") (name "Net-(IC4-LX)") (class "Default")
      (node (ref "D4") (pin "C") (pinfunction "C_C") (pintype "passive"))
      (node (ref "IC4") (pin "1") (pinfunction "LX_1") (pintype "passive"))
      (node (ref "L2") (pin "2") (pinfunction "2_2") (pintype "passive"))
      (node (ref "R15") (pin "2") (pinfunction "2_2") (pintype "passive"))
    )
    (net (code "57") (name "Net-(IC4-SS)") (class "Default")
      (node (ref "C11") (pin "1") (pinfunction "1_1") (pintype "passive"))
      (node (ref "IC4") (pin "7") (pinfunction "SS_7") (pintype "passive"))
    )
    (net (code "58") (name "Net-(IC4-VIN)") (class "Default")
      (node (ref "C8") (pin "2") (pinfunction "2_2") (pintype "passive"))
      (node (ref "D2") (pin "C") (pinfunction "C_C") (pintype "passive"))
      (node (ref "IC4") (pin "EX_PAD") (pinfunction "VIN_EX_PAD") (pintype "power_in"))
      (node (ref "R8") (pin "2") (pinfunction "2_2") (pintype "passive"))
    )
    (net (code "59") (name "Net-(IC5-PROG)") (class "Default")
      (node (ref "IC5") (pin "5") (pinfunction "PROG_5") (pintype "passive"))
      (node (ref "R9") (pin "2") (pinfunction "2_2") (pintype "passive"))
    )
    (net (code "60") (name "Net-(IC5-STAT)") (class "Default")
      (node (ref "IC5") (pin "1") (pinfunction "STAT_1") (pintype "passive"))
      (node (ref "R14") (pin "2") (pinfunction "2_2") (pintype "passive"))
      (node (ref "R7") (pin "2") (pinfunction "2_2") (pintype "passive"))
    )
    (net (code "61") (name "Net-(IC6-EN)") (class "Default")
      (node (ref "C10") (pin "1") (pinfunction "1_1") (pintype "passive"))
      (node (ref "C7") (pin "1") (pinfunction "1_1") (pintype "passive"))
      (node (ref "IC6") (pin "6") (pinfunction "VBAT_6") (pintype "passive"))
      (node (ref "IC6") (pin "9") (pinfunction "EN_9") (pintype "passive"))
      (node (ref "IC8") (pin "5") (pinfunction "D_5") (pintype "passive"))
      (node (ref "IC8") (pin "6") (pinfunction "D_6") (pintype "passive"))
      (node (ref "IC8") (pin "7") (pinfunction "D_7") (pintype "passive"))
      (node (ref "IC8") (pin "8") (pinfunction "D_8") (pintype "passive"))
      (node (ref "L1") (pin "2") (pinfunction "2_2") (pintype "passive"))
      (node (ref "R11") (pin "2") (pinfunction "2_2") (pintype "passive"))
    )
    (net (code "62") (name "Net-(IC6-LBI)") (class "Default")
      (node (ref "IC6") (pin "7") (pinfunction "LBI_7") (pintype "passive"))
      (node (ref "R11") (pin "1") (pinfunction "1_1") (pintype "passive"))
      (node (ref "R12") (pin "2") (pinfunction "2_2") (pintype "passive"))
    )
    (net (code "63") (name "Net-(IC6-LBO)") (class "Default")
      (node (ref "IC6") (pin "10") (pinfunction "LBO_10") (pintype "passive"))
      (node (ref "R16") (pin "1") (pinfunction "1_1") (pintype "passive"))
      (node (ref "R17") (pin "1") (pinfunction "1_1") (pintype "passive"))
      (node (ref "R28") (pin "2") (pinfunction "2_2") (pintype "passive"))
    )
    (net (code "64") (name "Net-(IC6-SW-Pad1)") (class "Default")
      (node (ref "IC6") (pin "1") (pinfunction "SW_1") (pintype "passive"))
      (node (ref "IC6") (pin "2") (pinfunction "SW_2") (pintype "passive"))
      (node (ref "L1") (pin "1") (pinfunction "1_1") (pintype "passive"))
    )
    (net (code "65") (name "Net-(IC7-IN1+)") (class "Default")
      (node (ref "IC7") (pin "7") (pinfunction "IN1+_7") (pintype "input"))
      (node (ref "VR1") (pin "2") (pinfunction "2_2") (pintype "passive"))
    )
    (net (code "66") (name "Net-(IC7-IN1-)") (class "Default")
      (node (ref "C17") (pin "+") (pinfunction "+_+") (pintype "passive"))
      (node (ref "IC7") (pin "8") (pinfunction "IN1-_8") (pintype "input"))
    )
    (net (code "67") (name "Net-(IC7-IN2+)") (class "Default")
      (node (ref "IC7") (pin "6") (pinfunction "IN2+_6") (pintype "input"))
      (node (ref "VR2") (pin "2") (pinfunction "2_2") (pintype "passive"))
    )
    (net (code "68") (name "Net-(IC7-IN2-)") (class "Default")
      (node (ref "C18") (pin "+") (pinfunction "+_+") (pintype "passive"))
      (node (ref "IC7") (pin "5") (pinfunction "IN2-_5") (pintype "input"))
    )
    (net (code "69") (name "Net-(IC7-OUT1)") (class "Default")
      (node (ref "C22") (pin "+") (pinfunction "+_+") (pintype "passive"))
      (node (ref "IC7") (pin "1") (pinfunction "OUT1_1") (pintype "output"))
    )
    (net (code "70") (name "Net-(IC7-OUT2)") (class "Default")
      (node (ref "C23") (pin "+") (pinfunction "+_+") (pintype "passive"))
      (node (ref "IC7") (pin "3") (pinfunction "OUT2_3") (pintype "output"))
    )
    (net (code "71") (name "Net-(IC8-G)") (class "Default")
      (node (ref "C27") (pin "1") (pinfunction "1_1") (pintype "passive"))
      (node (ref "IC8") (pin "4") (pinfunction "G_4") (pintype "passive"))
      (node (ref "J1") (pin "2") (pinfunction "2_2") (pintype "passive"))
      (node (ref "R6") (pin "1") (pinfunction "1_1") (pintype "passive"))
    )
    (net (code "72") (name "Net-(JP5-Pad4)") (class "Default")
      (node (ref "JP5") (pin "4") (pinfunction "4_4") (pintype "passive"))
      (node (ref "R22") (pin "1") (pinfunction "1_1") (pintype "passive"))
    )
    (net (code "73") (name "Net-(JP5-Pad5)") (class "Default")
      (node (ref "JP5") (pin "5") (pinfunction "5_5") (pintype "passive"))
      (node (ref "R24") (pin "1") (pinfunction "1_1") (pintype "passive"))
    )
    (net (code "74") (name "Net-(Q2-GATE)") (class "Default")
      (node (ref "Q2") (pin "G") (pinfunction "GATE_G") (pintype "bidirectional"))
      (node (ref "Q3") (pin "3") (pinfunction "OUT_3") (pintype "passive"))
      (node (ref "R1") (pin "2") (pinfunction "2_2") (pintype "passive"))
    )
    (net (code "75") (name "Net-(U$1-GPIO4{slash}GPCLK0)") (class "Default")
      (node (ref "C28") (pin "1") (pinfunction "1_1") (pintype "passive"))
      (node (ref "SW3") (pin "1") (pinfunction "1_1") (pintype "passive"))
      (node (ref "U$1") (pin "P1_7") (pinfunction "GPIO4/GPCLK0_P1_7") (pintype "bidirectional"))
    )
    (net (code "76") (name "Net-(U$1-RESET)") (class "Default")
      (node (ref "C1") (pin "1") (pinfunction "1_1") (pintype "passive"))
      (node (ref "SW1") (pin "2") (pinfunction "2_2") (pintype "passive"))
      (node (ref "U$1") (pin "P6_1") (pinfunction "RESET_P6_1") (pintype "power_in"))
    )
    (net (code "77") (name "Net-(ZD2-K)") (class "Default")
      (node (ref "IC10") (pin "7") (pinfunction "7_7") (pintype "output"))
      (node (ref "IC10") (pin "8") (pinfunction "8_8") (pintype "output"))
      (node (ref "JP7") (pin "1") (pinfunction "1_1") (pintype "passive"))
      (node (ref "ZD2") (pin "C") (pinfunction "K_C") (pintype "passive"))
    )
    (net (code "78") (name "Net-(ZD3-K)") (class "Default")
      (node (ref "IC10") (pin "5") (pinfunction "5_5") (pintype "output"))
      (node (ref "IC10") (pin "6") (pinfunction "6_6") (pintype "output"))
      (node (ref "JP7") (pin "2") (pinfunction "2_2") (pintype "passive"))
      (node (ref "ZD3") (pin "C") (pinfunction "K_C") (pintype "passive"))
    )
    (net (code "79") (name "unconnected-(IC2-SDO-Pad6)") (class "Default")
      (node (ref "IC2") (pin "6") (pinfunction "SDO_6") (pintype "output"))
    )
    (net (code "80") (name "unconnected-(IC6-FB-Pad12)") (class "Default")
      (node (ref "IC6") (pin "12") (pinfunction "FB_12") (pintype "passive"))
    )
    (net (code "81") (name "unconnected-(IC6-NC-Pad16)") (class "Default")
      (node (ref "IC6") (pin "16") (pinfunction "NC_16") (pintype "no_connect"))
    )
    (net (code "82") (name "unconnected-(IC10-Pad2)") (class "Default")
      (node (ref "IC10") (pin "2") (pinfunction "2_2") (pintype "bidirectional"))
    )
    (net (code "83") (name "unconnected-(IC10-Pad4)") (class "Default")
      (node (ref "IC10") (pin "4") (pinfunction "4_4") (pintype "bidirectional"))
    )
    (net (code "84") (name "unconnected-(J3-Pad4)") (class "Default")
      (node (ref "J3") (pin "4") (pinfunction "4_4") (pintype "passive"))
    )
    (net (code "85") (name "unconnected-(LCD1-3V3_OUT-Pad21)") (class "Default")
      (node (ref "LCD1") (pin "21") (pinfunction "3V3_OUT_21") (pintype "passive"))
    )
    (net (code "86") (name "unconnected-(LCD1-5V_IN-Pad1)") (class "Default")
      (node (ref "LCD1") (pin "1") (pinfunction "5V_IN_1") (pintype "passive"))
    )
    (net (code "87") (name "unconnected-(LCD1-NC-Pad7)") (class "Default")
      (node (ref "LCD1") (pin "7") (pinfunction "NC_7") (pintype "no_connect"))
    )
    (net (code "88") (name "unconnected-(LCD1-NC-Pad8)") (class "Default")
      (node (ref "LCD1") (pin "8") (pinfunction "NC_8") (pintype "no_connect"))
    )
    (net (code "89") (name "unconnected-(LCD1-NC-Pad9)") (class "Default")
      (node (ref "LCD1") (pin "9") (pinfunction "NC_9") (pintype "no_connect"))
    )
    (net (code "90") (name "unconnected-(LCD1-NC-Pad10)") (class "Default")
      (node (ref "LCD1") (pin "10") (pinfunction "NC_10") (pintype "no_connect"))
    )
    (net (code "91") (name "unconnected-(LCD1-NC-Pad11)") (class "Default")
      (node (ref "LCD1") (pin "11") (pinfunction "NC_11") (pintype "no_connect"))
    )
    (net (code "92") (name "unconnected-(LCD1-NC-Pad12)") (class "Default")
      (node (ref "LCD1") (pin "12") (pinfunction "NC_12") (pintype "no_connect"))
    )
    (net (code "93") (name "unconnected-(LCD1-NC-Pad13)") (class "Default")
      (node (ref "LCD1") (pin "13") (pinfunction "NC_13") (pintype "no_connect"))
    )
    (net (code "94") (name "unconnected-(LCD1-NC-Pad14)") (class "Default")
      (node (ref "LCD1") (pin "14") (pinfunction "NC_14") (pintype "no_connect"))
    )
    (net (code "95") (name "unconnected-(LCD1-NC-Pad16)") (class "Default")
      (node (ref "LCD1") (pin "16") (pinfunction "NC_16") (pintype "no_connect"))
    )
    (net (code "96") (name "unconnected-(LCD1-NC-Pad17)") (class "Default")
      (node (ref "LCD1") (pin "17") (pinfunction "NC_17") (pintype "no_connect"))
    )
    (net (code "97") (name "unconnected-(LCD1-NC-Pad18)") (class "Default")
      (node (ref "LCD1") (pin "18") (pinfunction "NC_18") (pintype "no_connect"))
    )
    (net (code "98") (name "unconnected-(LCD1-NC-Pad23)") (class "Default")
      (node (ref "LCD1") (pin "23") (pinfunction "NC_23") (pintype "no_connect"))
    )
    (net (code "99") (name "unconnected-(LCD1-NC-Pad24)") (class "Default")
      (node (ref "LCD1") (pin "24") (pinfunction "NC_24") (pintype "no_connect"))
    )
    (net (code "100") (name "unconnected-(LCD1-NC-Pad25)") (class "Default")
      (node (ref "LCD1") (pin "25") (pinfunction "NC_25") (pintype "no_connect"))
    )
    (net (code "101") (name "unconnected-(LCD1-NC-Pad26)") (class "Default")
      (node (ref "LCD1") (pin "26") (pinfunction "NC_26") (pintype "no_connect"))
    )
    (net (code "102") (name "unconnected-(LCD1-NC-Pad27)") (class "Default")
      (node (ref "LCD1") (pin "27") (pinfunction "NC_27") (pintype "no_connect"))
    )
    (net (code "103") (name "unconnected-(LCD1-NC-Pad28)") (class "Default")
      (node (ref "LCD1") (pin "28") (pinfunction "NC_28") (pintype "no_connect"))
    )
    (net (code "104") (name "unconnected-(LCD1-NC-Pad29)") (class "Default")
      (node (ref "LCD1") (pin "29") (pinfunction "NC_29") (pintype "no_connect"))
    )
    (net (code "105") (name "unconnected-(LCD1-NC-Pad30)") (class "Default")
      (node (ref "LCD1") (pin "30") (pinfunction "NC_30") (pintype "no_connect"))
    )
    (net (code "106") (name "unconnected-(LCD1-NC-Pad31)") (class "Default")
      (node (ref "LCD1") (pin "31") (pinfunction "NC_31") (pintype "no_connect"))
    )
    (net (code "107") (name "unconnected-(LCD1-NC-Pad37)") (class "Default")
      (node (ref "LCD1") (pin "37") (pinfunction "NC_37") (pintype "no_connect"))
    )
    (net (code "108") (name "unconnected-(LCD1-NC-Pad38)") (class "Default")
      (node (ref "LCD1") (pin "38") (pinfunction "NC_38") (pintype "no_connect"))
    )
    (net (code "109") (name "unconnected-(U1-KEY-Pad26)") (class "Default")
      (node (ref "U1") (pin "26") (pinfunction "KEY_26") (pintype "input"))
    )
    (net (code "110") (name "unconnected-(U1-LED-Pad24)") (class "Default")
      (node (ref "U1") (pin "24") (pinfunction "LED_24") (pintype "output"))
    )
  )
)
